# sensors.net
KiCad netlist of a schematic drawn in EAGLE
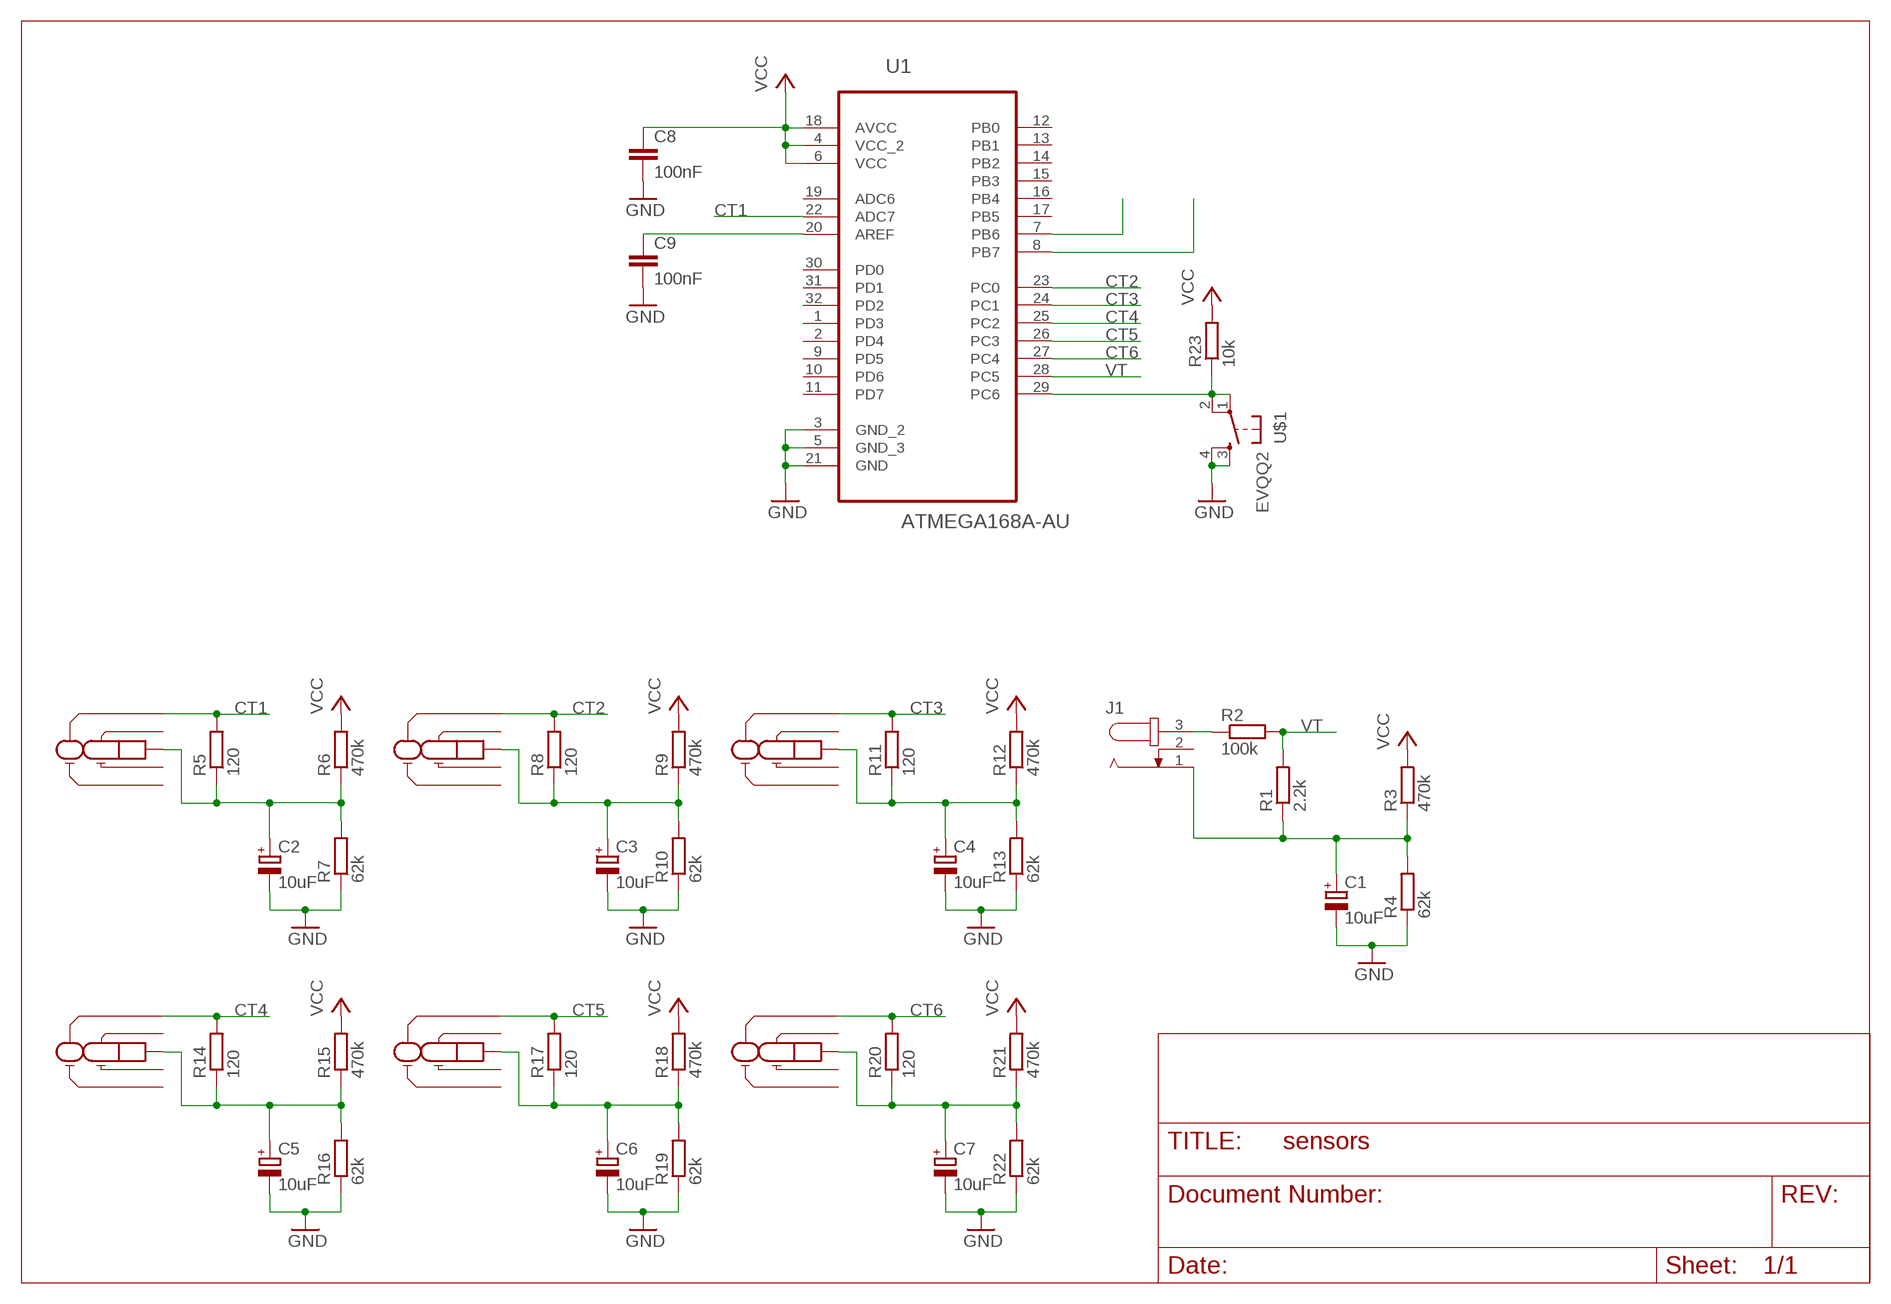
[diagram p0: schematic, sheet 1]

(export (version "E")
  (design (tool "Eeschema 10.0.6"))
  (components
    (comp (ref "C1")
      (value "10uF")
      (footprint "eagle-import:153CLV-0405")
      (libsource (lib "eagle-import") (part "CPOL-EU153CLV-0405"))
    )
    (comp (ref "C2")
      (value "10uF")
      (footprint "eagle-import:153CLV-0405")
      (libsource (lib "eagle-import") (part "CPOL-EU153CLV-0405"))
    )
    (comp (ref "C3")
      (value "10uF")
      (footprint "eagle-import:153CLV-0405")
      (libsource (lib "eagle-import") (part "CPOL-EU153CLV-0405"))
    )
    (comp (ref "C4")
      (value "10uF")
      (footprint "eagle-import:153CLV-0405")
      (libsource (lib "eagle-import") (part "CPOL-EU153CLV-0405"))
    )
    (comp (ref "C5")
      (value "10uF")
      (footprint "eagle-import:153CLV-0405")
      (libsource (lib "eagle-import") (part "CPOL-EU153CLV-0405"))
    )
    (comp (ref "C6")
      (value "10uF")
      (footprint "eagle-import:153CLV-0405")
      (libsource (lib "eagle-import") (part "CPOL-EU153CLV-0405"))
    )
    (comp (ref "C7")
      (value "10uF")
      (footprint "eagle-import:153CLV-0405")
      (libsource (lib "eagle-import") (part "CPOL-EU153CLV-0405"))
    )
    (comp (ref "C8")
      (value "100nF")
      (footprint "eagle-import:C1206")
      (libsource (lib "eagle-import") (part "C-EUC1206"))
    )
    (comp (ref "C9")
      (value "100nF")
      (footprint "eagle-import:C1206")
      (libsource (lib "eagle-import") (part "C-EUC1206"))
    )
    (comp (ref "J1")
      (value "JACK-PLUG0")
      (footprint "eagle-import:SPC4077")
      (libsource (lib "eagle-import") (part "JACK-PLUG0"))
    )
    (comp (ref "JC1")
      (value "15428/BT")
      (footprint "eagle-import:15428_BT")
      (libsource (lib "eagle-import") (part "15428/BT"))
    )
    (comp (ref "JC2")
      (value "15428/BT")
      (footprint "eagle-import:15428_BT@1")
      (libsource (lib "eagle-import") (part "Jack3.5_15428/BT"))
    )
    (comp (ref "JC3")
      (value "15428/BT")
      (footprint "eagle-import:15428_BT@1")
      (libsource (lib "eagle-import") (part "Jack3.5_15428/BT"))
    )
    (comp (ref "JC4")
      (value "15428/BT")
      (footprint "eagle-import:15428_BT@1")
      (libsource (lib "eagle-import") (part "Jack3.5_15428/BT"))
    )
    (comp (ref "JC5")
      (value "15428/BT")
      (footprint "eagle-import:15428_BT@1")
      (libsource (lib "eagle-import") (part "Jack3.5_15428/BT"))
    )
    (comp (ref "JC6")
      (value "15428/BT")
      (footprint "eagle-import:15428_BT@1")
      (libsource (lib "eagle-import") (part "Jack3.5_15428/BT"))
    )
    (comp (ref "R1")
      (value "2.2k")
      (footprint "eagle-import:R1206")
      (libsource (lib "eagle-import") (part "R-EU_R1206"))
    )
    (comp (ref "R2")
      (value "100k")
      (footprint "eagle-import:R1206")
      (libsource (lib "eagle-import") (part "R-EU_R1206"))
    )
    (comp (ref "R3")
      (value "470k")
      (footprint "eagle-import:R1206")
      (libsource (lib "eagle-import") (part "R-EU_R1206"))
    )
    (comp (ref "R4")
      (value "62k")
      (footprint "eagle-import:R1206")
      (libsource (lib "eagle-import") (part "R-EU_R1206"))
    )
    (comp (ref "R5")
      (value "120")
      (footprint "eagle-import:R1206")
      (libsource (lib "eagle-import") (part "R-EU_R1206"))
    )
    (comp (ref "R6")
      (value "470k")
      (footprint "eagle-import:R1206")
      (libsource (lib "eagle-import") (part "R-EU_R1206"))
    )
    (comp (ref "R7")
      (value "62k")
      (footprint "eagle-import:R1206")
      (libsource (lib "eagle-import") (part "R-EU_R1206"))
    )
    (comp (ref "R8")
      (value "120")
      (footprint "eagle-import:R1206")
      (libsource (lib "eagle-import") (part "R-EU_R1206"))
    )
    (comp (ref "R9")
      (value "470k")
      (footprint "eagle-import:R1206")
      (libsource (lib "eagle-import") (part "R-EU_R1206"))
    )
    (comp (ref "R10")
      (value "62k")
      (footprint "eagle-import:R1206")
      (libsource (lib "eagle-import") (part "R-EU_R1206"))
    )
    (comp (ref "R11")
      (value "120")
      (footprint "eagle-import:R1206")
      (libsource (lib "eagle-import") (part "R-EU_R1206"))
    )
    (comp (ref "R12")
      (value "470k")
      (footprint "eagle-import:R1206")
      (libsource (lib "eagle-import") (part "R-EU_R1206"))
    )
    (comp (ref "R13")
      (value "62k")
      (footprint "eagle-import:R1206")
      (libsource (lib "eagle-import") (part "R-EU_R1206"))
    )
    (comp (ref "R14")
      (value "120")
      (footprint "eagle-import:R1206")
      (libsource (lib "eagle-import") (part "R-EU_R1206"))
    )
    (comp (ref "R15")
      (value "470k")
      (footprint "eagle-import:R1206")
      (libsource (lib "eagle-import") (part "R-EU_R1206"))
    )
    (comp (ref "R16")
      (value "62k")
      (footprint "eagle-import:R1206")
      (libsource (lib "eagle-import") (part "R-EU_R1206"))
    )
    (comp (ref "R17")
      (value "120")
      (footprint "eagle-import:R1206")
      (libsource (lib "eagle-import") (part "R-EU_R1206"))
    )
    (comp (ref "R18")
      (value "470k")
      (footprint "eagle-import:R1206")
      (libsource (lib "eagle-import") (part "R-EU_R1206"))
    )
    (comp (ref "R19")
      (value "62k")
      (footprint "eagle-import:R1206")
      (libsource (lib "eagle-import") (part "R-EU_R1206"))
    )
    (comp (ref "R20")
      (value "120")
      (footprint "eagle-import:R1206")
      (libsource (lib "eagle-import") (part "R-EU_R1206"))
    )
    (comp (ref "R21")
      (value "470k")
      (footprint "eagle-import:R1206")
      (libsource (lib "eagle-import") (part "R-EU_R1206"))
    )
    (comp (ref "R22")
      (value "62k")
      (footprint "eagle-import:R1206")
      (libsource (lib "eagle-import") (part "R-EU_R1206"))
    )
    (comp (ref "R23")
      (value "10k")
      (footprint "eagle-import:R1206")
      (libsource (lib "eagle-import") (part "R-EU_R1206"))
    )
    (comp (ref "U$1")
      (value "EVQQ2")
      (footprint "eagle-import:EVQQ2")
      (libsource (lib "eagle-import") (part "EVQQ2"))
    )
    (comp (ref "U1")
      (value "ATMEGA168A-AU")
      (footprint "eagle-import:QFP80P900X900X120-32N")
      (libsource (lib "eagle-import") (part "ATMEGA168A-AU"))
    )
  )
  (nets
    (net (code "1") (name "/CT1") (class "Default")
      (node (ref "JC1") (pin "P2") (pinfunction "P2_P2") (pintype "output"))
      (node (ref "R5") (pin "2") (pinfunction "2_2") (pintype "passive"))
      (node (ref "U1") (pin "22") (pinfunction "ADC7_22") (pintype "input"))
    )
    (net (code "2") (name "/CT2") (class "Default")
      (node (ref "JC2") (pin "P2") (pinfunction "P2_P2") (pintype "output"))
      (node (ref "R8") (pin "2") (pinfunction "2_2") (pintype "passive"))
      (node (ref "U1") (pin "23") (pinfunction "PC0_23") (pintype "bidirectional"))
    )
    (net (code "3") (name "/CT3") (class "Default")
      (node (ref "JC3") (pin "P2") (pinfunction "P2_P2") (pintype "output"))
      (node (ref "R11") (pin "2") (pinfunction "2_2") (pintype "passive"))
      (node (ref "U1") (pin "24") (pinfunction "PC1_24") (pintype "bidirectional"))
    )
    (net (code "4") (name "/CT4") (class "Default")
      (node (ref "JC4") (pin "P2") (pinfunction "P2_P2") (pintype "output"))
      (node (ref "R14") (pin "2") (pinfunction "2_2") (pintype "passive"))
      (node (ref "U1") (pin "25") (pinfunction "PC2_25") (pintype "bidirectional"))
    )
    (net (code "5") (name "/CT5") (class "Default")
      (node (ref "JC5") (pin "P2") (pinfunction "P2_P2") (pintype "output"))
      (node (ref "R17") (pin "2") (pinfunction "2_2") (pintype "passive"))
      (node (ref "U1") (pin "26") (pinfunction "PC3_26") (pintype "bidirectional"))
    )
    (net (code "6") (name "/CT6") (class "Default")
      (node (ref "JC6") (pin "P2") (pinfunction "P2_P2") (pintype "output"))
      (node (ref "R20") (pin "2") (pinfunction "2_2") (pintype "passive"))
      (node (ref "U1") (pin "27") (pinfunction "PC4_27") (pintype "bidirectional"))
    )
    (net (code "7") (name "/VT") (class "Default")
      (node (ref "R1") (pin "2") (pinfunction "2_2") (pintype "passive"))
      (node (ref "R2") (pin "2") (pinfunction "2_2") (pintype "passive"))
      (node (ref "U1") (pin "28") (pinfunction "PC5_28") (pintype "bidirectional"))
    )
    (net (code "8") (name "GND") (class "Default")
      (node (ref "C1") (pin "-") (pinfunction "-_-") (pintype "passive"))
      (node (ref "C2") (pin "-") (pinfunction "-_-") (pintype "passive"))
      (node (ref "C3") (pin "-") (pinfunction "-_-") (pintype "passive"))
      (node (ref "C4") (pin "-") (pinfunction "-_-") (pintype "passive"))
      (node (ref "C5") (pin "-") (pinfunction "-_-") (pintype "passive"))
      (node (ref "C6") (pin "-") (pinfunction "-_-") (pintype "passive"))
      (node (ref "C7") (pin "-") (pinfunction "-_-") (pintype "passive"))
      (node (ref "C8") (pin "2") (pinfunction "2_2") (pintype "passive"))
      (node (ref "C9") (pin "2") (pinfunction "2_2") (pintype "passive"))
      (node (ref "R10") (pin "1") (pinfunction "1_1") (pintype "passive"))
      (node (ref "R13") (pin "1") (pinfunction "1_1") (pintype "passive"))
      (node (ref "R16") (pin "1") (pinfunction "1_1") (pintype "passive"))
      (node (ref "R19") (pin "1") (pinfunction "1_1") (pintype "passive"))
      (node (ref "R22") (pin "1") (pinfunction "1_1") (pintype "passive"))
      (node (ref "R4") (pin "1") (pinfunction "1_1") (pintype "passive"))
      (node (ref "R7") (pin "1") (pinfunction "1_1") (pintype "passive"))
      (node (ref "U$1") (pin "3") (pinfunction "3_3") (pintype "passive"))
      (node (ref "U$1") (pin "4") (pinfunction "4_4") (pintype "passive"))
      (node (ref "U1") (pin "21") (pinfunction "GND_21") (pintype "passive"))
      (node (ref "U1") (pin "3") (pinfunction "GND_2_3") (pintype "passive"))
      (node (ref "U1") (pin "5") (pinfunction "GND_3_5") (pintype "passive"))
    )
    (net (code "9") (name "Net-(C1-Pad+)") (class "Default")
      (node (ref "C1") (pin "+") (pinfunction "+_+") (pintype "passive"))
      (node (ref "J1") (pin "1") (pinfunction "1_1") (pintype "passive"))
      (node (ref "R1") (pin "1") (pinfunction "1_1") (pintype "passive"))
      (node (ref "R3") (pin "1") (pinfunction "1_1") (pintype "passive"))
      (node (ref "R4") (pin "2") (pinfunction "2_2") (pintype "passive"))
    )
    (net (code "10") (name "Net-(C2-Pad+)") (class "Default")
      (node (ref "C2") (pin "+") (pinfunction "+_+") (pintype "passive"))
      (node (ref "JC1") (pin "P1") (pinfunction "P1_P1") (pintype "output"))
      (node (ref "R5") (pin "1") (pinfunction "1_1") (pintype "passive"))
      (node (ref "R6") (pin "1") (pinfunction "1_1") (pintype "passive"))
      (node (ref "R7") (pin "2") (pinfunction "2_2") (pintype "passive"))
    )
    (net (code "11") (name "Net-(C3-Pad+)") (class "Default")
      (node (ref "C3") (pin "+") (pinfunction "+_+") (pintype "passive"))
      (node (ref "JC2") (pin "P1") (pinfunction "P1_P1") (pintype "output"))
      (node (ref "R10") (pin "2") (pinfunction "2_2") (pintype "passive"))
      (node (ref "R8") (pin "1") (pinfunction "1_1") (pintype "passive"))
      (node (ref "R9") (pin "1") (pinfunction "1_1") (pintype "passive"))
    )
    (net (code "12") (name "Net-(C4-Pad+)") (class "Default")
      (node (ref "C4") (pin "+") (pinfunction "+_+") (pintype "passive"))
      (node (ref "JC3") (pin "P1") (pinfunction "P1_P1") (pintype "output"))
      (node (ref "R11") (pin "1") (pinfunction "1_1") (pintype "passive"))
      (node (ref "R12") (pin "1") (pinfunction "1_1") (pintype "passive"))
      (node (ref "R13") (pin "2") (pinfunction "2_2") (pintype "passive"))
    )
    (net (code "13") (name "Net-(C5-Pad+)") (class "Default")
      (node (ref "C5") (pin "+") (pinfunction "+_+") (pintype "passive"))
      (node (ref "JC4") (pin "P1") (pinfunction "P1_P1") (pintype "output"))
      (node (ref "R14") (pin "1") (pinfunction "1_1") (pintype "passive"))
      (node (ref "R15") (pin "1") (pinfunction "1_1") (pintype "passive"))
      (node (ref "R16") (pin "2") (pinfunction "2_2") (pintype "passive"))
    )
    (net (code "14") (name "Net-(C6-Pad+)") (class "Default")
      (node (ref "C6") (pin "+") (pinfunction "+_+") (pintype "passive"))
      (node (ref "JC5") (pin "P1") (pinfunction "P1_P1") (pintype "output"))
      (node (ref "R17") (pin "1") (pinfunction "1_1") (pintype "passive"))
      (node (ref "R18") (pin "1") (pinfunction "1_1") (pintype "passive"))
      (node (ref "R19") (pin "2") (pinfunction "2_2") (pintype "passive"))
    )
    (net (code "15") (name "Net-(C7-Pad+)") (class "Default")
      (node (ref "C7") (pin "+") (pinfunction "+_+") (pintype "passive"))
      (node (ref "JC6") (pin "P1") (pinfunction "P1_P1") (pintype "output"))
      (node (ref "R20") (pin "1") (pinfunction "1_1") (pintype "passive"))
      (node (ref "R21") (pin "1") (pinfunction "1_1") (pintype "passive"))
      (node (ref "R22") (pin "2") (pinfunction "2_2") (pintype "passive"))
    )
    (net (code "16") (name "Net-(J1-Pad3)") (class "Default")
      (node (ref "J1") (pin "3") (pinfunction "3_3") (pintype "passive"))
      (node (ref "R2") (pin "1") (pinfunction "1_1") (pintype "passive"))
    )
    (net (code "17") (name "Net-(U1-AREF)") (class "Default")
      (node (ref "C9") (pin "1") (pinfunction "1_1") (pintype "passive"))
      (node (ref "U1") (pin "20") (pinfunction "AREF_20") (pintype "input"))
    )
    (net (code "18") (name "Net-(U1-PC6)") (class "Default")
      (node (ref "R23") (pin "1") (pinfunction "1_1") (pintype "passive"))
      (node (ref "U$1") (pin "1") (pinfunction "1_1") (pintype "passive"))
      (node (ref "U$1") (pin "2") (pinfunction "2_2") (pintype "passive"))
      (node (ref "U1") (pin "29") (pinfunction "PC6_29") (pintype "bidirectional"))
    )
    (net (code "19") (name "VCC") (class "Default")
      (node (ref "C8") (pin "1") (pinfunction "1_1") (pintype "passive"))
      (node (ref "R12") (pin "2") (pinfunction "2_2") (pintype "passive"))
      (node (ref "R15") (pin "2") (pinfunction "2_2") (pintype "passive"))
      (node (ref "R18") (pin "2") (pinfunction "2_2") (pintype "passive"))
      (node (ref "R21") (pin "2") (pinfunction "2_2") (pintype "passive"))
      (node (ref "R23") (pin "2") (pinfunction "2_2") (pintype "passive"))
      (node (ref "R3") (pin "2") (pinfunction "2_2") (pintype "passive"))
      (node (ref "R6") (pin "2") (pinfunction "2_2") (pintype "passive"))
      (node (ref "R9") (pin "2") (pinfunction "2_2") (pintype "passive"))
      (node (ref "U1") (pin "18") (pinfunction "AVCC_18") (pintype "power_in"))
      (node (ref "U1") (pin "4") (pinfunction "VCC_2_4") (pintype "power_in"))
      (node (ref "U1") (pin "6") (pinfunction "VCC_6") (pintype "power_in"))
    )
    (net (code "20") (name "unconnected-(J1-Pad2)") (class "Default")
      (node (ref "J1") (pin "2") (pinfunction "2_2") (pintype "passive"))
    )
    (net (code "21") (name "unconnected-(JC1-PadP3)") (class "Default")
      (node (ref "JC1") (pin "P3") (pinfunction "P3_P3") (pintype "output"))
    )
    (net (code "22") (name "unconnected-(JC1-PadP4)") (class "Default")
      (node (ref "JC1") (pin "P4") (pinfunction "P4_P4") (pintype "output"))
    )
    (net (code "23") (name "unconnected-(JC1-PadP5)") (class "Default")
      (node (ref "JC1") (pin "P5") (pinfunction "P5_P5") (pintype "output"))
    )
    (net (code "24") (name "unconnected-(JC2-PadP3)") (class "Default")
      (node (ref "JC2") (pin "P3") (pinfunction "P3_P3") (pintype "output"))
    )
    (net (code "25") (name "unconnected-(JC2-PadP4)") (class "Default")
      (node (ref "JC2") (pin "P4") (pinfunction "P4_P4") (pintype "output"))
    )
    (net (code "26") (name "unconnected-(JC2-PadP5)") (class "Default")
      (node (ref "JC2") (pin "P5") (pinfunction "P5_P5") (pintype "output"))
    )
    (net (code "27") (name "unconnected-(JC3-PadP3)") (class "Default")
      (node (ref "JC3") (pin "P3") (pinfunction "P3_P3") (pintype "output"))
    )
    (net (code "28") (name "unconnected-(JC3-PadP4)") (class "Default")
      (node (ref "JC3") (pin "P4") (pinfunction "P4_P4") (pintype "output"))
    )
    (net (code "29") (name "unconnected-(JC3-PadP5)") (class "Default")
      (node (ref "JC3") (pin "P5") (pinfunction "P5_P5") (pintype "output"))
    )
    (net (code "30") (name "unconnected-(JC4-PadP3)") (class "Default")
      (node (ref "JC4") (pin "P3") (pinfunction "P3_P3") (pintype "output"))
    )
    (net (code "31") (name "unconnected-(JC4-PadP4)") (class "Default")
      (node (ref "JC4") (pin "P4") (pinfunction "P4_P4") (pintype "output"))
    )
    (net (code "32") (name "unconnected-(JC4-PadP5)") (class "Default")
      (node (ref "JC4") (pin "P5") (pinfunction "P5_P5") (pintype "output"))
    )
    (net (code "33") (name "unconnected-(JC5-PadP3)") (class "Default")
      (node (ref "JC5") (pin "P3") (pinfunction "P3_P3") (pintype "output"))
    )
    (net (code "34") (name "unconnected-(JC5-PadP4)") (class "Default")
      (node (ref "JC5") (pin "P4") (pinfunction "P4_P4") (pintype "output"))
    )
    (net (code "35") (name "unconnected-(JC5-PadP5)") (class "Default")
      (node (ref "JC5") (pin "P5") (pinfunction "P5_P5") (pintype "output"))
    )
    (net (code "36") (name "unconnected-(JC6-PadP3)") (class "Default")
      (node (ref "JC6") (pin "P3") (pinfunction "P3_P3") (pintype "output"))
    )
    (net (code "37") (name "unconnected-(JC6-PadP4)") (class "Default")
      (node (ref "JC6") (pin "P4") (pinfunction "P4_P4") (pintype "output"))
    )
    (net (code "38") (name "unconnected-(JC6-PadP5)") (class "Default")
      (node (ref "JC6") (pin "P5") (pinfunction "P5_P5") (pintype "output"))
    )
    (net (code "39") (name "unconnected-(U1-ADC6-Pad19)") (class "Default")
      (node (ref "U1") (pin "19") (pinfunction "ADC6_19") (pintype "input"))
    )
    (net (code "40") (name "unconnected-(U1-PB0-Pad12)") (class "Default")
      (node (ref "U1") (pin "12") (pinfunction "PB0_12") (pintype "bidirectional"))
    )
    (net (code "41") (name "unconnected-(U1-PB1-Pad13)") (class "Default")
      (node (ref "U1") (pin "13") (pinfunction "PB1_13") (pintype "bidirectional"))
    )
    (net (code "42") (name "unconnected-(U1-PB2-Pad14)") (class "Default")
      (node (ref "U1") (pin "14") (pinfunction "PB2_14") (pintype "bidirectional"))
    )
    (net (code "43") (name "unconnected-(U1-PB3-Pad15)") (class "Default")
      (node (ref "U1") (pin "15") (pinfunction "PB3_15") (pintype "bidirectional"))
    )
    (net (code "44") (name "unconnected-(U1-PB4-Pad16)") (class "Default")
      (node (ref "U1") (pin "16") (pinfunction "PB4_16") (pintype "bidirectional"))
    )
    (net (code "45") (name "unconnected-(U1-PB5-Pad17)") (class "Default")
      (node (ref "U1") (pin "17") (pinfunction "PB5_17") (pintype "bidirectional"))
    )
    (net (code "46") (name "unconnected-(U1-PB6-Pad7)") (class "Default")
      (node (ref "U1") (pin "7") (pinfunction "PB6_7") (pintype "bidirectional"))
    )
    (net (code "47") (name "unconnected-(U1-PB7-Pad8)") (class "Default")
      (node (ref "U1") (pin "8") (pinfunction "PB7_8") (pintype "bidirectional"))
    )
    (net (code "48") (name "unconnected-(U1-PD0-Pad30)") (class "Default")
      (node (ref "U1") (pin "30") (pinfunction "PD0_30") (pintype "bidirectional"))
    )
    (net (code "49") (name "unconnected-(U1-PD1-Pad31)") (class "Default")
      (node (ref "U1") (pin "31") (pinfunction "PD1_31") (pintype "bidirectional"))
    )
    (net (code "50") (name "unconnected-(U1-PD2-Pad32)") (class "Default")
      (node (ref "U1") (pin "32") (pinfunction "PD2_32") (pintype "bidirectional"))
    )
    (net (code "51") (name "unconnected-(U1-PD3-Pad1)") (class "Default")
      (node (ref "U1") (pin "1") (pinfunction "PD3_1") (pintype "bidirectional"))
    )
    (net (code "52") (name "unconnected-(U1-PD4-Pad2)") (class "Default")
      (node (ref "U1") (pin "2") (pinfunction "PD4_2") (pintype "bidirectional"))
    )
    (net (code "53") (name "unconnected-(U1-PD5-Pad9)") (class "Default")
      (node (ref "U1") (pin "9") (pinfunction "PD5_9") (pintype "bidirectional"))
    )
    (net (code "54") (name "unconnected-(U1-PD6-Pad10)") (class "Default")
      (node (ref "U1") (pin "10") (pinfunction "PD6_10") (pintype "bidirectional"))
    )
    (net (code "55") (name "unconnected-(U1-PD7-Pad11)") (class "Default")
      (node (ref "U1") (pin "11") (pinfunction "PD7_11") (pintype "bidirectional"))
    )
  )
)
